# 1_Controller.net
KiCad netlist of a schematic drawn in Altium Designer
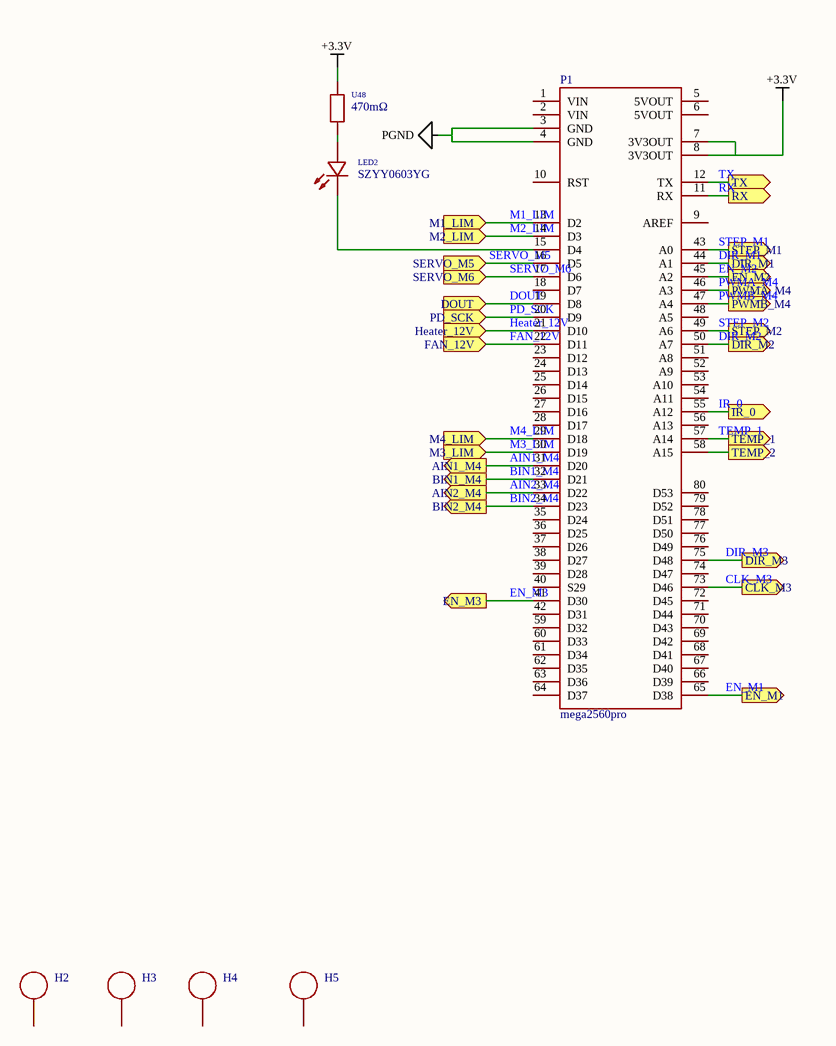
[diagram p0: 1_Controller.schdoc]

(export (version "E")
  (design (tool "Eeschema 10.0.6"))
  (components
    (comp (ref "H2")
      (value "HOLE_D3M5_D7M0_PAD_PTH")
      (footprint "HOLE_D3M5_D7M0_PAD_PTH")
      (libsource (lib "altium-import") (part "root_3_HOLE_D3M5_D7M0_PAD_PTH_"))
    )
    (comp (ref "H3")
      (value "HOLE_D3M5_D7M0_PAD_PTH")
      (footprint "HOLE_D3M5_D7M0_PAD_PTH")
      (libsource (lib "altium-import") (part "root_3_HOLE_D3M5_D7M0_PAD_PTH_"))
    )
    (comp (ref "H4")
      (value "HOLE_D3M5_D7M0_PAD_PTH")
      (footprint "HOLE_D3M5_D7M0_PAD_PTH")
      (libsource (lib "altium-import") (part "root_3_HOLE_D3M5_D7M0_PAD_PTH_"))
    )
    (comp (ref "H5")
      (value "HOLE_D3M5_D7M0_PAD_PTH")
      (footprint "HOLE_D3M5_D7M0_PAD_PTH")
      (libsource (lib "altium-import") (part "root_3_HOLE_D3M5_D7M0_PAD_PTH_"))
    )
    (comp (ref "LED2")
      (value "SZYY0603YG")
      (footprint "LED0603-R-RD_GREEN")
      (description "Emitted Color:Green-yellow")
      (fields (field (name "MANUFACTURER") "yongyu(永裕光电)"))
      (libsource (lib "altium-import") (part "root_1_SZYY0603YG_"))
    )
    (comp (ref "P1")
      (value "mega2560pro")
      (footprint "MEGA2560PRO")
      (libsource (lib "altium-import") (part "root_0_MEGA2560PRO_"))
    )
    (comp (ref "U48")
      (value "470mΩ")
      (footprint "R0603")
      (fields
        (field (name "MANUFACTURER") "FOJAN(富捷)")
        (field (name "MANUFACTURER PART") "FRL0603FR470TS")
        (field (name "TOLERANCE") "±1%")
      )
      (libsource (lib "altium-import") (part "root_1_FRL0603FR470TS_"))
    )
  )
  (nets
    (net (code "1") (name "+3.3V") (class "Default")
      (node (ref "P1") (pin "7") (pinfunction "3V3OUT_7") (pintype "passive"))
      (node (ref "P1") (pin "8") (pinfunction "3V3OUT_8") (pintype "passive"))
      (node (ref "U48") (pin "2") (pinfunction "2_2") (pintype "passive"))
    )
    (net (code "2") (name "/AIN1_M4") (class "Default")
      (node (ref "P1") (pin "31") (pinfunction "D20_31") (pintype "passive"))
    )
    (net (code "3") (name "/AIN2_M4") (class "Default")
      (node (ref "P1") (pin "33") (pinfunction "D22_33") (pintype "passive"))
    )
    (net (code "4") (name "/BIN1_M4") (class "Default")
      (node (ref "P1") (pin "32") (pinfunction "D21_32") (pintype "passive"))
    )
    (net (code "5") (name "/BIN2_M4") (class "Default")
      (node (ref "P1") (pin "34") (pinfunction "D23_34") (pintype "passive"))
    )
    (net (code "6") (name "/CLK_M3") (class "Default")
      (node (ref "P1") (pin "73") (pinfunction "D46_73") (pintype "passive"))
    )
    (net (code "7") (name "/DIR_M1") (class "Default")
      (node (ref "P1") (pin "44") (pinfunction "A1_44") (pintype "passive"))
    )
    (net (code "8") (name "/DIR_M2") (class "Default")
      (node (ref "P1") (pin "50") (pinfunction "A7_50") (pintype "passive"))
    )
    (net (code "9") (name "/DIR_M3") (class "Default")
      (node (ref "P1") (pin "75") (pinfunction "D48_75") (pintype "passive"))
    )
    (net (code "10") (name "/DOUT") (class "Default")
      (node (ref "P1") (pin "19") (pinfunction "D8_19") (pintype "passive"))
    )
    (net (code "11") (name "/EN_M1") (class "Default")
      (node (ref "P1") (pin "65") (pinfunction "D38_65") (pintype "passive"))
    )
    (net (code "12") (name "/EN_M2") (class "Default")
      (node (ref "P1") (pin "45") (pinfunction "A2_45") (pintype "passive"))
    )
    (net (code "13") (name "/EN_M3") (class "Default")
      (node (ref "P1") (pin "41") (pinfunction "D30_41") (pintype "passive"))
    )
    (net (code "14") (name "/FAN_12V") (class "Default")
      (node (ref "P1") (pin "22") (pinfunction "D11_22") (pintype "passive"))
    )
    (net (code "15") (name "/Heater_12V") (class "Default")
      (node (ref "P1") (pin "21") (pinfunction "D10_21") (pintype "passive"))
    )
    (net (code "16") (name "/IR_0") (class "Default")
      (node (ref "P1") (pin "55") (pinfunction "A12_55") (pintype "passive"))
    )
    (net (code "17") (name "/M1_LIM") (class "Default")
      (node (ref "P1") (pin "13") (pinfunction "D2_13") (pintype "passive"))
    )
    (net (code "18") (name "/M2_LIM") (class "Default")
      (node (ref "P1") (pin "14") (pinfunction "D3_14") (pintype "passive"))
    )
    (net (code "19") (name "/M3_LIM") (class "Default")
      (node (ref "P1") (pin "30") (pinfunction "D19_30") (pintype "passive"))
    )
    (net (code "20") (name "/M4_LIM") (class "Default")
      (node (ref "P1") (pin "29") (pinfunction "D18_29") (pintype "passive"))
    )
    (net (code "21") (name "/PD_SCK") (class "Default")
      (node (ref "P1") (pin "20") (pinfunction "D9_20") (pintype "passive"))
    )
    (net (code "22") (name "/PWMA_M4") (class "Default")
      (node (ref "P1") (pin "46") (pinfunction "A3_46") (pintype "passive"))
    )
    (net (code "23") (name "/PWMB_M4") (class "Default")
      (node (ref "P1") (pin "47") (pinfunction "A4_47") (pintype "passive"))
    )
    (net (code "24") (name "/RX") (class "Default")
      (node (ref "P1") (pin "11") (pinfunction "RX_11") (pintype "passive"))
    )
    (net (code "25") (name "/SERVO_M5") (class "Default")
      (node (ref "P1") (pin "16") (pinfunction "D5_16") (pintype "passive"))
    )
    (net (code "26") (name "/SERVO_M6") (class "Default")
      (node (ref "P1") (pin "17") (pinfunction "D6_17") (pintype "passive"))
    )
    (net (code "27") (name "/STEP_M1") (class "Default")
      (node (ref "P1") (pin "43") (pinfunction "A0_43") (pintype "passive"))
    )
    (net (code "28") (name "/STEP_M2") (class "Default")
      (node (ref "P1") (pin "49") (pinfunction "A6_49") (pintype "passive"))
    )
    (net (code "29") (name "/TEMP_1") (class "Default")
      (node (ref "P1") (pin "57") (pinfunction "A14_57") (pintype "passive"))
    )
    (net (code "30") (name "/TEMP_2") (class "Default")
      (node (ref "P1") (pin "58") (pinfunction "A15_58") (pintype "passive"))
    )
    (net (code "31") (name "/TX") (class "Default")
      (node (ref "P1") (pin "12") (pinfunction "TX_12") (pintype "passive"))
    )
    (net (code "32") (name "Net-(LED2-+)") (class "Default")
      (node (ref "LED2") (pin "1") (pinfunction "+_1") (pintype "passive"))
      (node (ref "U48") (pin "1") (pinfunction "1_1") (pintype "passive"))
    )
    (net (code "33") (name "Net-(LED2--)") (class "Default")
      (node (ref "LED2") (pin "2") (pinfunction "-_2") (pintype "passive"))
      (node (ref "P1") (pin "15") (pinfunction "D4_15") (pintype "passive"))
    )
    (net (code "34") (name "PGND") (class "Default")
      (node (ref "P1") (pin "3") (pinfunction "GND_3") (pintype "passive"))
      (node (ref "P1") (pin "4") (pinfunction "GND_4") (pintype "passive"))
    )
    (net (code "35") (name "unconnected-(H2-Pad1)") (class "Default")
      (node (ref "H2") (pin "1") (pinfunction "1_1") (pintype "passive"))
    )
    (net (code "36") (name "unconnected-(H3-Pad1)") (class "Default")
      (node (ref "H3") (pin "1") (pinfunction "1_1") (pintype "passive"))
    )
    (net (code "37") (name "unconnected-(H4-Pad1)") (class "Default")
      (node (ref "H4") (pin "1") (pinfunction "1_1") (pintype "passive"))
    )
    (net (code "38") (name "unconnected-(H5-Pad1)") (class "Default")
      (node (ref "H5") (pin "1") (pinfunction "1_1") (pintype "passive"))
    )
    (net (code "39") (name "unconnected-(P1-5VOUT-Pad5)") (class "Default")
      (node (ref "P1") (pin "5") (pinfunction "5VOUT_5") (pintype "passive"))
    )
    (net (code "40") (name "unconnected-(P1-5VOUT-Pad6)") (class "Default")
      (node (ref "P1") (pin "6") (pinfunction "5VOUT_6") (pintype "passive"))
    )
    (net (code "41") (name "unconnected-(P1-A5-Pad48)") (class "Default")
      (node (ref "P1") (pin "48") (pinfunction "A5_48") (pintype "passive"))
    )
    (net (code "42") (name "unconnected-(P1-A8-Pad51)") (class "Default")
      (node (ref "P1") (pin "51") (pinfunction "A8_51") (pintype "passive"))
    )
    (net (code "43") (name "unconnected-(P1-A9-Pad52)") (class "Default")
      (node (ref "P1") (pin "52") (pinfunction "A9_52") (pintype "passive"))
    )
    (net (code "44") (name "unconnected-(P1-A10-Pad53)") (class "Default")
      (node (ref "P1") (pin "53") (pinfunction "A10_53") (pintype "passive"))
    )
    (net (code "45") (name "unconnected-(P1-A11-Pad54)") (class "Default")
      (node (ref "P1") (pin "54") (pinfunction "A11_54") (pintype "passive"))
    )
    (net (code "46") (name "unconnected-(P1-A13-Pad56)") (class "Default")
      (node (ref "P1") (pin "56") (pinfunction "A13_56") (pintype "passive"))
    )
    (net (code "47") (name "unconnected-(P1-AREF-Pad9)") (class "Default")
      (node (ref "P1") (pin "9") (pinfunction "AREF_9") (pintype "passive"))
    )
    (net (code "48") (name "unconnected-(P1-D7-Pad18)") (class "Default")
      (node (ref "P1") (pin "18") (pinfunction "D7_18") (pintype "passive"))
    )
    (net (code "49") (name "unconnected-(P1-D12-Pad23)") (class "Default")
      (node (ref "P1") (pin "23") (pinfunction "D12_23") (pintype "passive"))
    )
    (net (code "50") (name "unconnected-(P1-D13-Pad24)") (class "Default")
      (node (ref "P1") (pin "24") (pinfunction "D13_24") (pintype "passive"))
    )
    (net (code "51") (name "unconnected-(P1-D14-Pad25)") (class "Default")
      (node (ref "P1") (pin "25") (pinfunction "D14_25") (pintype "passive"))
    )
    (net (code "52") (name "unconnected-(P1-D15-Pad26)") (class "Default")
      (node (ref "P1") (pin "26") (pinfunction "D15_26") (pintype "passive"))
    )
    (net (code "53") (name "unconnected-(P1-D16-Pad27)") (class "Default")
      (node (ref "P1") (pin "27") (pinfunction "D16_27") (pintype "passive"))
    )
    (net (code "54") (name "unconnected-(P1-D17-Pad28)") (class "Default")
      (node (ref "P1") (pin "28") (pinfunction "D17_28") (pintype "passive"))
    )
    (net (code "55") (name "unconnected-(P1-D24-Pad35)") (class "Default")
      (node (ref "P1") (pin "35") (pinfunction "D24_35") (pintype "passive"))
    )
    (net (code "56") (name "unconnected-(P1-D25-Pad36)") (class "Default")
      (node (ref "P1") (pin "36") (pinfunction "D25_36") (pintype "passive"))
    )
    (net (code "57") (name "unconnected-(P1-D26-Pad37)") (class "Default")
      (node (ref "P1") (pin "37") (pinfunction "D26_37") (pintype "passive"))
    )
    (net (code "58") (name "unconnected-(P1-D27-Pad38)") (class "Default")
      (node (ref "P1") (pin "38") (pinfunction "D27_38") (pintype "passive"))
    )
    (net (code "59") (name "unconnected-(P1-D28-Pad39)") (class "Default")
      (node (ref "P1") (pin "39") (pinfunction "D28_39") (pintype "passive"))
    )
    (net (code "60") (name "unconnected-(P1-D31-Pad42)") (class "Default")
      (node (ref "P1") (pin "42") (pinfunction "D31_42") (pintype "passive"))
    )
    (net (code "61") (name "unconnected-(P1-D32-Pad59)") (class "Default")
      (node (ref "P1") (pin "59") (pinfunction "D32_59") (pintype "passive"))
    )
    (net (code "62") (name "unconnected-(P1-D33-Pad60)") (class "Default")
      (node (ref "P1") (pin "60") (pinfunction "D33_60") (pintype "passive"))
    )
    (net (code "63") (name "unconnected-(P1-D34-Pad61)") (class "Default")
      (node (ref "P1") (pin "61") (pinfunction "D34_61") (pintype "passive"))
    )
    (net (code "64") (name "unconnected-(P1-D35-Pad62)") (class "Default")
      (node (ref "P1") (pin "62") (pinfunction "D35_62") (pintype "passive"))
    )
    (net (code "65") (name "unconnected-(P1-D36-Pad63)") (class "Default")
      (node (ref "P1") (pin "63") (pinfunction "D36_63") (pintype "passive"))
    )
    (net (code "66") (name "unconnected-(P1-D37-Pad64)") (class "Default")
      (node (ref "P1") (pin "64") (pinfunction "D37_64") (pintype "passive"))
    )
    (net (code "67") (name "unconnected-(P1-D39-Pad66)") (class "Default")
      (node (ref "P1") (pin "66") (pinfunction "D39_66") (pintype "passive"))
    )
    (net (code "68") (name "unconnected-(P1-D40-Pad67)") (class "Default")
      (node (ref "P1") (pin "67") (pinfunction "D40_67") (pintype "passive"))
    )
    (net (code "69") (name "unconnected-(P1-D41-Pad68)") (class "Default")
      (node (ref "P1") (pin "68") (pinfunction "D41_68") (pintype "passive"))
    )
    (net (code "70") (name "unconnected-(P1-D42-Pad69)") (class "Default")
      (node (ref "P1") (pin "69") (pinfunction "D42_69") (pintype "passive"))
    )
    (net (code "71") (name "unconnected-(P1-D43-Pad70)") (class "Default")
      (node (ref "P1") (pin "70") (pinfunction "D43_70") (pintype "passive"))
    )
    (net (code "72") (name "unconnected-(P1-D44-Pad71)") (class "Default")
      (node (ref "P1") (pin "71") (pinfunction "D44_71") (pintype "passive"))
    )
    (net (code "73") (name "unconnected-(P1-D45-Pad72)") (class "Default")
      (node (ref "P1") (pin "72") (pinfunction "D45_72") (pintype "passive"))
    )
    (net (code "74") (name "unconnected-(P1-D47-Pad74)") (class "Default")
      (node (ref "P1") (pin "74") (pinfunction "D47_74") (pintype "passive"))
    )
    (net (code "75") (name "unconnected-(P1-D49-Pad76)") (class "Default")
      (node (ref "P1") (pin "76") (pinfunction "D49_76") (pintype "passive"))
    )
    (net (code "76") (name "unconnected-(P1-D50-Pad77)") (class "Default")
      (node (ref "P1") (pin "77") (pinfunction "D50_77") (pintype "passive"))
    )
    (net (code "77") (name "unconnected-(P1-D51-Pad78)") (class "Default")
      (node (ref "P1") (pin "78") (pinfunction "D51_78") (pintype "passive"))
    )
    (net (code "78") (name "unconnected-(P1-D52-Pad79)") (class "Default")
      (node (ref "P1") (pin "79") (pinfunction "D52_79") (pintype "passive"))
    )
    (net (code "79") (name "unconnected-(P1-D53-Pad80)") (class "Default")
      (node (ref "P1") (pin "80") (pinfunction "D53_80") (pintype "passive"))
    )
    (net (code "80") (name "unconnected-(P1-RST-Pad10)") (class "Default")
      (node (ref "P1") (pin "10") (pinfunction "RST_10") (pintype "passive"))
    )
    (net (code "81") (name "unconnected-(P1-S29-Pad40)") (class "Default")
      (node (ref "P1") (pin "40") (pinfunction "S29_40") (pintype "passive"))
    )
    (net (code "82") (name "unconnected-(P1-VIN-Pad1)") (class "Default")
      (node (ref "P1") (pin "1") (pinfunction "VIN_1") (pintype "passive"))
    )
    (net (code "83") (name "unconnected-(P1-VIN-Pad2)") (class "Default")
      (node (ref "P1") (pin "2") (pinfunction "VIN_2") (pintype "passive"))
    )
  )
)
